# pendulumControl.net
KiCad netlist of a schematic drawn in EAGLE
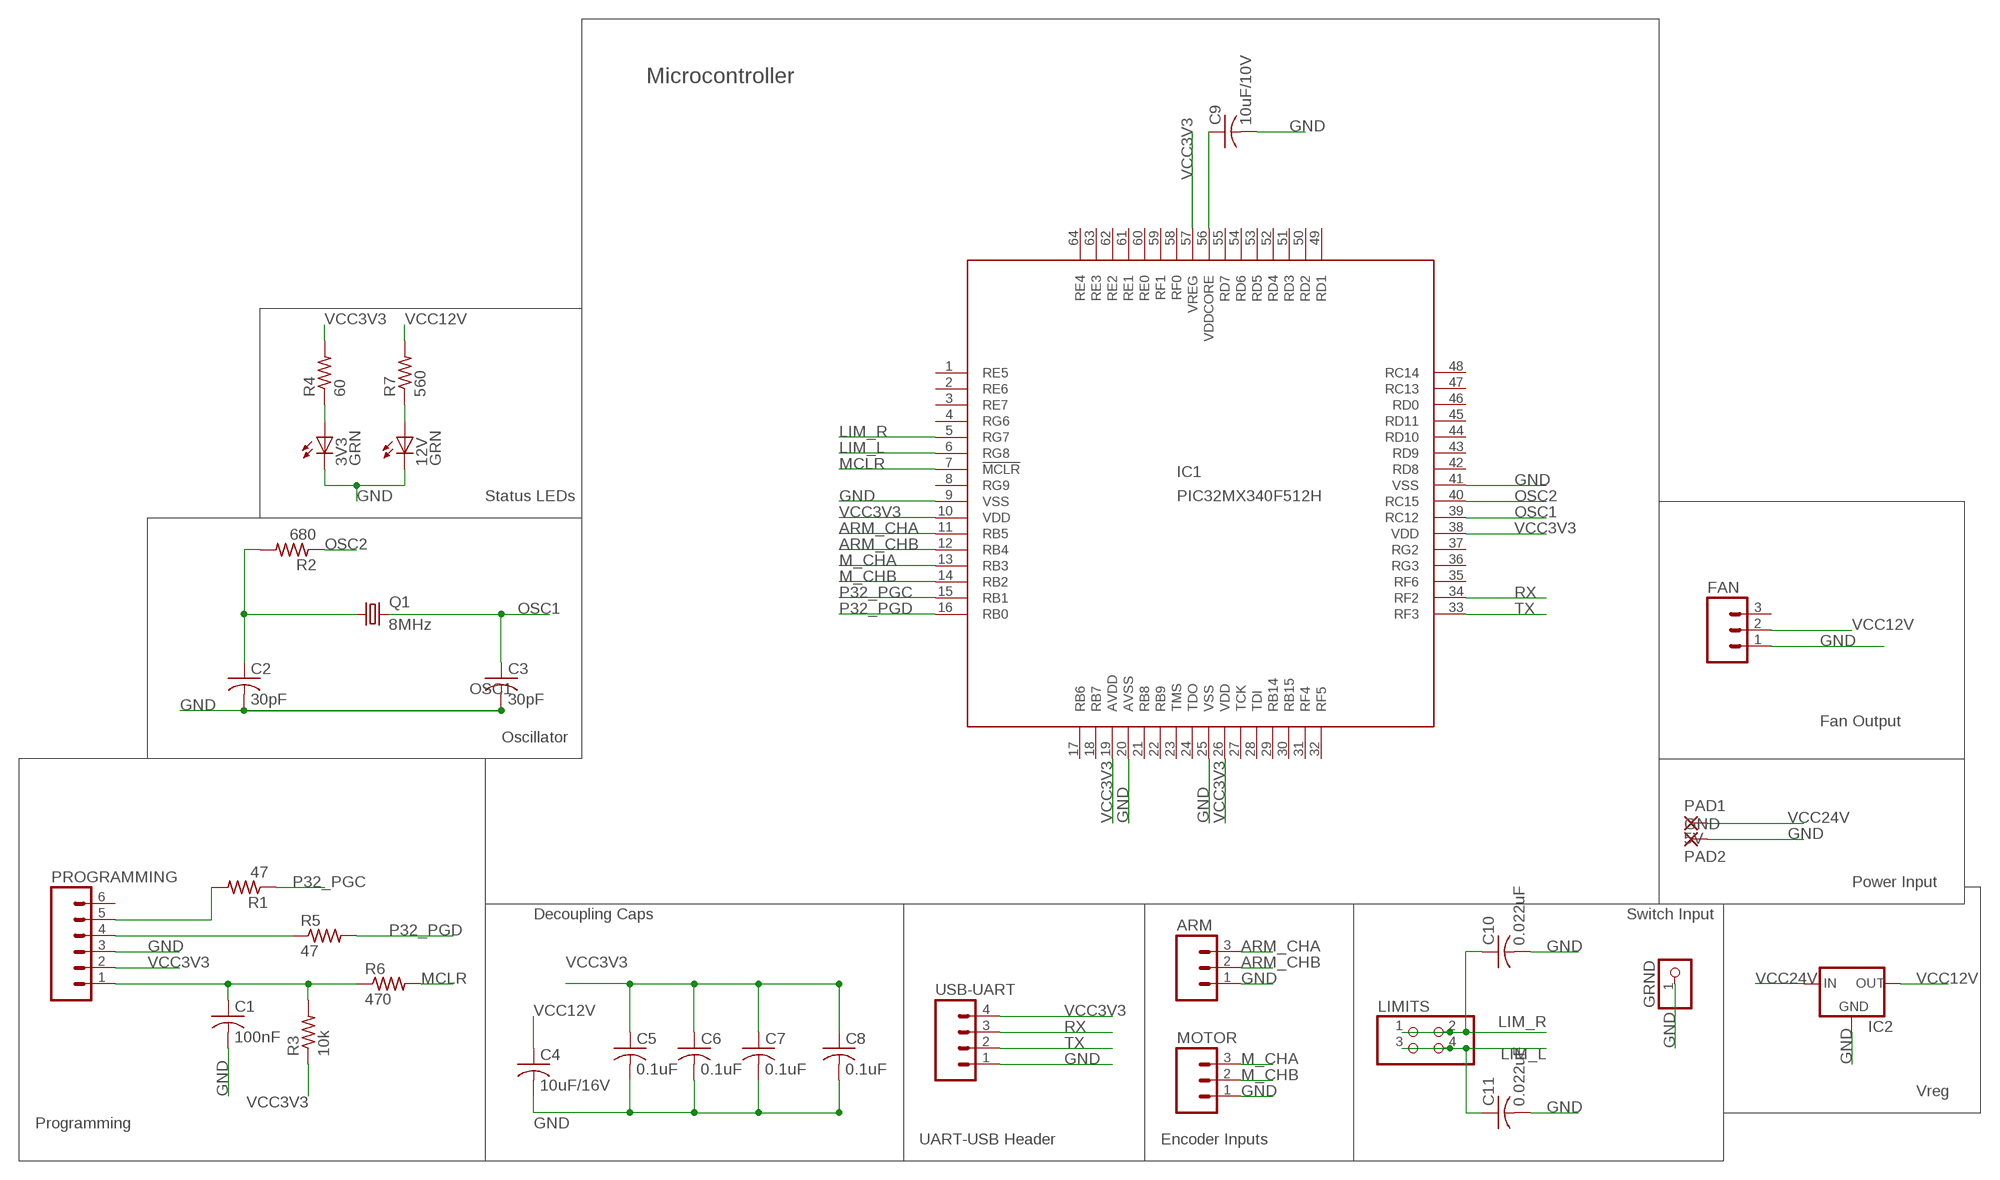
[diagram p0: schematic, sheet 1]

(export (version "E")
  (design (tool "Eeschema 10.0.6"))
  (components
    (comp (ref "3V3")
      (value "GRN")
      (footprint "eagle-import:CHIP-LED0805")
      (libsource (lib "eagle-import") (part "LEDCHIP-LED0805"))
    )
    (comp (ref "12V")
      (value "GRN")
      (footprint "eagle-import:CHIP-LED0805")
      (libsource (lib "eagle-import") (part "LEDCHIP-LED0805"))
    )
    (comp (ref "ARM")
      (value "M03PTH")
      (footprint "eagle-import:1X03")
      (libsource (lib "eagle-import") (part "M03PTH"))
    )
    (comp (ref "C1")
      (value "100nF")
      (footprint "eagle-import:C0805")
      (libsource (lib "eagle-import") (part "C-USC0805"))
    )
    (comp (ref "C2")
      (value "30pF")
      (footprint "eagle-import:C0805")
      (libsource (lib "eagle-import") (part "C-USC0805"))
    )
    (comp (ref "C3")
      (value "30pF")
      (footprint "eagle-import:C0805")
      (libsource (lib "eagle-import") (part "C-USC0805"))
    )
    (comp (ref "C4")
      (value "10uF/16V")
      (footprint "eagle-import:C0805")
      (libsource (lib "eagle-import") (part "C-USC0805"))
    )
    (comp (ref "C5")
      (value "0.1uF")
      (footprint "eagle-import:C0805")
      (libsource (lib "eagle-import") (part "C-USC0805"))
    )
    (comp (ref "C6")
      (value "0.1uF")
      (footprint "eagle-import:C0805")
      (libsource (lib "eagle-import") (part "resistor_C-USC0805"))
    )
    (comp (ref "C7")
      (value "0.1uF")
      (footprint "eagle-import:C0805")
      (libsource (lib "eagle-import") (part "resistor_C-USC0805"))
    )
    (comp (ref "C8")
      (value "0.1uF")
      (footprint "eagle-import:C0805")
      (libsource (lib "eagle-import") (part "resistor_C-USC0805"))
    )
    (comp (ref "C9")
      (value "10uF/10V")
      (footprint "eagle-import:C0805")
      (libsource (lib "eagle-import") (part "C-USC0805"))
    )
    (comp (ref "C10")
      (value "0.022uF")
      (footprint "eagle-import:C0805")
      (libsource (lib "eagle-import") (part "C-USC0805"))
    )
    (comp (ref "C11")
      (value "0.022uF")
      (footprint "eagle-import:C0805")
      (libsource (lib "eagle-import") (part "C-USC0805"))
    )
    (comp (ref "FAN")
      (value "M03POLAR")
      (footprint "eagle-import:MOLEX-1X3")
      (libsource (lib "eagle-import") (part "M03POLAR"))
    )
    (comp (ref "GRND")
      (value "PINHD-1X1")
      (footprint "eagle-import:1X01")
      (libsource (lib "eagle-import") (part "PINHD-1X1"))
    )
    (comp (ref "IC1")
      (value "PIC32MX340F512H")
      (footprint "eagle-import:TQFP64-10X10")
      (fields (field (name "MPN") "PIC32MX340F512H-80I/PT"))
      (libsource (lib "eagle-import") (part "PIC32MX340FH512"))
    )
    (comp (ref "IC2")
      (value "78MXXS")
      (footprint "eagle-import:78MXXS")
      (libsource (lib "eagle-import") (part "78MXXS"))
    )
    (comp (ref "LIMITS")
      (value "PINHD-2X2")
      (footprint "eagle-import:2X02")
      (libsource (lib "eagle-import") (part "PINHD-2X2"))
    )
    (comp (ref "MOTOR")
      (value "M03PTH")
      (footprint "eagle-import:1X03")
      (libsource (lib "eagle-import") (part "M03PTH"))
    )
    (comp (ref "PAD1")
      (value "5V")
      (footprint "eagle-import:3,81_1,4")
      (libsource (lib "eagle-import") (part "3,81/1,4"))
    )
    (comp (ref "PAD2")
      (value "GND")
      (footprint "eagle-import:3,81_1,4")
      (libsource (lib "eagle-import") (part "3,81/1,4"))
    )
    (comp (ref "PROGRAMMING")
      (value "M06FEMALE_LOCK")
      (footprint "eagle-import:1X06_FEMALE_LOCK.010")
      (libsource (lib "eagle-import") (part "M06FEMALE_LOCK"))
    )
    (comp (ref "Q1")
      (value "8MHz")
      (footprint "eagle-import:HC49_S")
      (libsource (lib "eagle-import") (part "CRYSTALHC49S"))
    )
    (comp (ref "R1")
      (value "47")
      (footprint "eagle-import:R0805")
      (libsource (lib "eagle-import") (part "resistor_R-US_R0805"))
    )
    (comp (ref "R2")
      (value "680")
      (footprint "eagle-import:R0805")
      (libsource (lib "eagle-import") (part "R-US_R0805"))
    )
    (comp (ref "R3")
      (value "10k")
      (footprint "eagle-import:R0805")
      (libsource (lib "eagle-import") (part "resistor_R-US_R0805"))
    )
    (comp (ref "R4")
      (value "60")
      (footprint "eagle-import:R0805")
      (libsource (lib "eagle-import") (part "R-US_R0805"))
    )
    (comp (ref "R5")
      (value "47")
      (footprint "eagle-import:R0805")
      (libsource (lib "eagle-import") (part "resistor_R-US_R0805"))
    )
    (comp (ref "R6")
      (value "470")
      (footprint "eagle-import:R0805")
      (libsource (lib "eagle-import") (part "resistor_R-US_R0805"))
    )
    (comp (ref "R7")
      (value "560")
      (footprint "eagle-import:R0805")
      (libsource (lib "eagle-import") (part "R-US_R0805"))
    )
    (comp (ref "USB-UART")
      (value "M04PTH")
      (footprint "eagle-import:1X04")
      (libsource (lib "eagle-import") (part "M04PTH"))
    )
  )
  (nets
    (net (code "1") (name "/ARM_CHA") (class "Default")
      (node (ref "ARM") (pin "3") (pinfunction "3_3") (pintype "passive"))
      (node (ref "IC1") (pin "11") (pinfunction "RB5_11") (pintype "bidirectional"))
    )
    (net (code "2") (name "/ARM_CHB") (class "Default")
      (node (ref "ARM") (pin "2") (pinfunction "2_2") (pintype "passive"))
      (node (ref "IC1") (pin "12") (pinfunction "RB4_12") (pintype "bidirectional"))
    )
    (net (code "3") (name "/GND") (class "Default")
      (node (ref "12V") (pin "C") (pinfunction "C_C") (pintype "passive"))
      (node (ref "3V3") (pin "C") (pinfunction "C_C") (pintype "passive"))
      (node (ref "ARM") (pin "1") (pinfunction "1_1") (pintype "passive"))
      (node (ref "C1") (pin "2") (pinfunction "2_2") (pintype "passive"))
      (node (ref "C10") (pin "2") (pinfunction "2_2") (pintype "passive"))
      (node (ref "C11") (pin "2") (pinfunction "2_2") (pintype "passive"))
      (node (ref "C2") (pin "2") (pinfunction "2_2") (pintype "passive"))
      (node (ref "C3") (pin "2") (pinfunction "2_2") (pintype "passive"))
      (node (ref "C4") (pin "2") (pinfunction "2_2") (pintype "passive"))
      (node (ref "C5") (pin "2") (pinfunction "2_2") (pintype "passive"))
      (node (ref "C6") (pin "2") (pinfunction "2_2") (pintype "passive"))
      (node (ref "C7") (pin "2") (pinfunction "2_2") (pintype "passive"))
      (node (ref "C8") (pin "2") (pinfunction "2_2") (pintype "passive"))
      (node (ref "C9") (pin "2") (pinfunction "2_2") (pintype "passive"))
      (node (ref "FAN") (pin "1") (pinfunction "1_1") (pintype "passive"))
      (node (ref "GRND") (pin "1") (pinfunction "1_1") (pintype "passive"))
      (node (ref "IC1") (pin "20") (pinfunction "AVSS_20") (pintype "power_in"))
      (node (ref "IC1") (pin "25") (pinfunction "VSS_25") (pintype "power_in"))
      (node (ref "IC1") (pin "41") (pinfunction "VSS_41") (pintype "power_in"))
      (node (ref "IC1") (pin "9") (pinfunction "VSS_9") (pintype "power_in"))
      (node (ref "IC2") (pin "GND") (pinfunction "GND_GND") (pintype "input"))
      (node (ref "MOTOR") (pin "1") (pinfunction "1_1") (pintype "passive"))
      (node (ref "PAD2") (pin "1") (pinfunction "P_1") (pintype "passive"))
      (node (ref "PROGRAMMING") (pin "3") (pinfunction "3_3") (pintype "passive"))
      (node (ref "USB-UART") (pin "1") (pinfunction "1_1") (pintype "passive"))
    )
    (net (code "4") (name "/LIM_L") (class "Default")
      (node (ref "C11") (pin "1") (pinfunction "1_1") (pintype "passive"))
      (node (ref "IC1") (pin "6") (pinfunction "RG8_6") (pintype "bidirectional"))
      (node (ref "LIMITS") (pin "3") (pinfunction "3_3") (pintype "passive"))
      (node (ref "LIMITS") (pin "4") (pinfunction "4_4") (pintype "passive"))
    )
    (net (code "5") (name "/LIM_R") (class "Default")
      (node (ref "C10") (pin "1") (pinfunction "1_1") (pintype "passive"))
      (node (ref "IC1") (pin "5") (pinfunction "RG7_5") (pintype "bidirectional"))
      (node (ref "LIMITS") (pin "1") (pinfunction "1_1") (pintype "passive"))
      (node (ref "LIMITS") (pin "2") (pinfunction "2_2") (pintype "passive"))
    )
    (net (code "6") (name "/MCLR") (class "Default")
      (node (ref "IC1") (pin "7") (pinfunction "~{MCLR}_7") (pintype "input"))
      (node (ref "R6") (pin "2") (pinfunction "2_2") (pintype "passive"))
    )
    (net (code "7") (name "/M_CHA") (class "Default")
      (node (ref "IC1") (pin "13") (pinfunction "RB3_13") (pintype "bidirectional"))
      (node (ref "MOTOR") (pin "3") (pinfunction "3_3") (pintype "passive"))
    )
    (net (code "8") (name "/M_CHB") (class "Default")
      (node (ref "IC1") (pin "14") (pinfunction "RB2_14") (pintype "bidirectional"))
      (node (ref "MOTOR") (pin "2") (pinfunction "2_2") (pintype "passive"))
    )
    (net (code "9") (name "/OSC1") (class "Default")
      (node (ref "C3") (pin "1") (pinfunction "1_1") (pintype "passive"))
      (node (ref "IC1") (pin "39") (pinfunction "RC12_39") (pintype "bidirectional"))
      (node (ref "Q1") (pin "2") (pinfunction "2_2") (pintype "passive"))
    )
    (net (code "10") (name "/OSC2") (class "Default")
      (node (ref "IC1") (pin "40") (pinfunction "RC15_40") (pintype "bidirectional"))
      (node (ref "R2") (pin "1") (pinfunction "1_1") (pintype "passive"))
    )
    (net (code "11") (name "/P32_PGC") (class "Default")
      (node (ref "IC1") (pin "15") (pinfunction "RB1_15") (pintype "bidirectional"))
      (node (ref "R1") (pin "1") (pinfunction "1_1") (pintype "passive"))
    )
    (net (code "12") (name "/P32_PGD") (class "Default")
      (node (ref "IC1") (pin "16") (pinfunction "RB0_16") (pintype "bidirectional"))
      (node (ref "R5") (pin "2") (pinfunction "2_2") (pintype "passive"))
    )
    (net (code "13") (name "/RX") (class "Default")
      (node (ref "IC1") (pin "34") (pinfunction "RF2_34") (pintype "bidirectional"))
      (node (ref "USB-UART") (pin "3") (pinfunction "3_3") (pintype "passive"))
    )
    (net (code "14") (name "/TX") (class "Default")
      (node (ref "IC1") (pin "33") (pinfunction "RF3_33") (pintype "bidirectional"))
      (node (ref "USB-UART") (pin "2") (pinfunction "2_2") (pintype "passive"))
    )
    (net (code "15") (name "/VCC3V3") (class "Default")
      (node (ref "C5") (pin "1") (pinfunction "1_1") (pintype "passive"))
      (node (ref "C6") (pin "1") (pinfunction "1_1") (pintype "passive"))
      (node (ref "C7") (pin "1") (pinfunction "1_1") (pintype "passive"))
      (node (ref "C8") (pin "1") (pinfunction "1_1") (pintype "passive"))
      (node (ref "IC1") (pin "10") (pinfunction "VDD_10") (pintype "power_in"))
      (node (ref "IC1") (pin "19") (pinfunction "AVDD_19") (pintype "power_in"))
      (node (ref "IC1") (pin "26") (pinfunction "VDD_26") (pintype "power_in"))
      (node (ref "IC1") (pin "38") (pinfunction "VDD_38") (pintype "power_in"))
      (node (ref "IC1") (pin "57") (pinfunction "VREG_57") (pintype "passive"))
      (node (ref "PROGRAMMING") (pin "2") (pinfunction "2_2") (pintype "passive"))
      (node (ref "R3") (pin "1") (pinfunction "1_1") (pintype "passive"))
      (node (ref "R4") (pin "2") (pinfunction "2_2") (pintype "passive"))
      (node (ref "USB-UART") (pin "4") (pinfunction "4_4") (pintype "passive"))
    )
    (net (code "16") (name "/VCC12V") (class "Default")
      (node (ref "C4") (pin "1") (pinfunction "1_1") (pintype "passive"))
      (node (ref "FAN") (pin "2") (pinfunction "2_2") (pintype "passive"))
      (node (ref "IC2") (pin "OUT") (pinfunction "OUT_OUT") (pintype "passive"))
      (node (ref "R7") (pin "2") (pinfunction "2_2") (pintype "passive"))
    )
    (net (code "17") (name "/VCC24V") (class "Default")
      (node (ref "IC2") (pin "IN") (pinfunction "IN_IN") (pintype "input"))
      (node (ref "PAD1") (pin "1") (pinfunction "P_1") (pintype "passive"))
    )
    (net (code "18") (name "Net-(3V3-PadA)") (class "Default")
      (node (ref "3V3") (pin "A") (pinfunction "A_A") (pintype "passive"))
      (node (ref "R4") (pin "1") (pinfunction "1_1") (pintype "passive"))
    )
    (net (code "19") (name "Net-(12V-PadA)") (class "Default")
      (node (ref "12V") (pin "A") (pinfunction "A_A") (pintype "passive"))
      (node (ref "R7") (pin "1") (pinfunction "1_1") (pintype "passive"))
    )
    (net (code "20") (name "Net-(C1-Pad1)") (class "Default")
      (node (ref "C1") (pin "1") (pinfunction "1_1") (pintype "passive"))
      (node (ref "PROGRAMMING") (pin "1") (pinfunction "1_1") (pintype "passive"))
      (node (ref "R3") (pin "2") (pinfunction "2_2") (pintype "passive"))
      (node (ref "R6") (pin "1") (pinfunction "1_1") (pintype "passive"))
    )
    (net (code "21") (name "Net-(C2-Pad1)") (class "Default")
      (node (ref "C2") (pin "1") (pinfunction "1_1") (pintype "passive"))
      (node (ref "Q1") (pin "1") (pinfunction "1_1") (pintype "passive"))
      (node (ref "R2") (pin "2") (pinfunction "2_2") (pintype "passive"))
    )
    (net (code "22") (name "Net-(IC1-VDDCORE)") (class "Default")
      (node (ref "C9") (pin "1") (pinfunction "1_1") (pintype "passive"))
      (node (ref "IC1") (pin "56") (pinfunction "VDDCORE_56") (pintype "power_in"))
    )
    (net (code "23") (name "Net-(PROGRAMMING-Pad4)") (class "Default")
      (node (ref "PROGRAMMING") (pin "4") (pinfunction "4_4") (pintype "passive"))
      (node (ref "R5") (pin "1") (pinfunction "1_1") (pintype "passive"))
    )
    (net (code "24") (name "Net-(PROGRAMMING-Pad5)") (class "Default")
      (node (ref "PROGRAMMING") (pin "5") (pinfunction "5_5") (pintype "passive"))
      (node (ref "R1") (pin "2") (pinfunction "2_2") (pintype "passive"))
    )
    (net (code "25") (name "unconnected-(FAN-Pad3)") (class "Default")
      (node (ref "FAN") (pin "3") (pinfunction "3_3") (pintype "passive"))
    )
    (net (code "26") (name "unconnected-(IC1-RB6-Pad17)") (class "Default")
      (node (ref "IC1") (pin "17") (pinfunction "RB6_17") (pintype "bidirectional"))
    )
    (net (code "27") (name "unconnected-(IC1-RB7-Pad18)") (class "Default")
      (node (ref "IC1") (pin "18") (pinfunction "RB7_18") (pintype "bidirectional"))
    )
    (net (code "28") (name "unconnected-(IC1-RB8-Pad21)") (class "Default")
      (node (ref "IC1") (pin "21") (pinfunction "RB8_21") (pintype "bidirectional"))
    )
    (net (code "29") (name "unconnected-(IC1-RB9-Pad22)") (class "Default")
      (node (ref "IC1") (pin "22") (pinfunction "RB9_22") (pintype "bidirectional"))
    )
    (net (code "30") (name "unconnected-(IC1-RB14-Pad29)") (class "Default")
      (node (ref "IC1") (pin "29") (pinfunction "RB14_29") (pintype "bidirectional"))
    )
    (net (code "31") (name "unconnected-(IC1-RB15-Pad30)") (class "Default")
      (node (ref "IC1") (pin "30") (pinfunction "RB15_30") (pintype "bidirectional"))
    )
    (net (code "32") (name "unconnected-(IC1-RC13-Pad47)") (class "Default")
      (node (ref "IC1") (pin "47") (pinfunction "RC13_47") (pintype "bidirectional"))
    )
    (net (code "33") (name "unconnected-(IC1-RC14-Pad48)") (class "Default")
      (node (ref "IC1") (pin "48") (pinfunction "RC14_48") (pintype "bidirectional"))
    )
    (net (code "34") (name "unconnected-(IC1-RD0-Pad46)") (class "Default")
      (node (ref "IC1") (pin "46") (pinfunction "RD0_46") (pintype "bidirectional"))
    )
    (net (code "35") (name "unconnected-(IC1-RD1-Pad49)") (class "Default")
      (node (ref "IC1") (pin "49") (pinfunction "RD1_49") (pintype "bidirectional"))
    )
    (net (code "36") (name "unconnected-(IC1-RD2-Pad50)") (class "Default")
      (node (ref "IC1") (pin "50") (pinfunction "RD2_50") (pintype "bidirectional"))
    )
    (net (code "37") (name "unconnected-(IC1-RD3-Pad51)") (class "Default")
      (node (ref "IC1") (pin "51") (pinfunction "RD3_51") (pintype "bidirectional"))
    )
    (net (code "38") (name "unconnected-(IC1-RD4-Pad52)") (class "Default")
      (node (ref "IC1") (pin "52") (pinfunction "RD4_52") (pintype "bidirectional"))
    )
    (net (code "39") (name "unconnected-(IC1-RD5-Pad53)") (class "Default")
      (node (ref "IC1") (pin "53") (pinfunction "RD5_53") (pintype "bidirectional"))
    )
    (net (code "40") (name "unconnected-(IC1-RD6-Pad54)") (class "Default")
      (node (ref "IC1") (pin "54") (pinfunction "RD6_54") (pintype "bidirectional"))
    )
    (net (code "41") (name "unconnected-(IC1-RD7-Pad55)") (class "Default")
      (node (ref "IC1") (pin "55") (pinfunction "RD7_55") (pintype "bidirectional"))
    )
    (net (code "42") (name "unconnected-(IC1-RD8-Pad42)") (class "Default")
      (node (ref "IC1") (pin "42") (pinfunction "RD8_42") (pintype "bidirectional"))
    )
    (net (code "43") (name "unconnected-(IC1-RD9-Pad43)") (class "Default")
      (node (ref "IC1") (pin "43") (pinfunction "RD9_43") (pintype "bidirectional"))
    )
    (net (code "44") (name "unconnected-(IC1-RD10-Pad44)") (class "Default")
      (node (ref "IC1") (pin "44") (pinfunction "RD10_44") (pintype "bidirectional"))
    )
    (net (code "45") (name "unconnected-(IC1-RD11-Pad45)") (class "Default")
      (node (ref "IC1") (pin "45") (pinfunction "RD11_45") (pintype "bidirectional"))
    )
    (net (code "46") (name "unconnected-(IC1-RE0-Pad60)") (class "Default")
      (node (ref "IC1") (pin "60") (pinfunction "RE0_60") (pintype "bidirectional"))
    )
    (net (code "47") (name "unconnected-(IC1-RE1-Pad61)") (class "Default")
      (node (ref "IC1") (pin "61") (pinfunction "RE1_61") (pintype "bidirectional"))
    )
    (net (code "48") (name "unconnected-(IC1-RE2-Pad62)") (class "Default")
      (node (ref "IC1") (pin "62") (pinfunction "RE2_62") (pintype "bidirectional"))
    )
    (net (code "49") (name "unconnected-(IC1-RE3-Pad63)") (class "Default")
      (node (ref "IC1") (pin "63") (pinfunction "RE3_63") (pintype "bidirectional"))
    )
    (net (code "50") (name "unconnected-(IC1-RE4-Pad64)") (class "Default")
      (node (ref "IC1") (pin "64") (pinfunction "RE4_64") (pintype "bidirectional"))
    )
    (net (code "51") (name "unconnected-(IC1-RE5-Pad1)") (class "Default")
      (node (ref "IC1") (pin "1") (pinfunction "RE5_1") (pintype "bidirectional"))
    )
    (net (code "52") (name "unconnected-(IC1-RE6-Pad2)") (class "Default")
      (node (ref "IC1") (pin "2") (pinfunction "RE6_2") (pintype "bidirectional"))
    )
    (net (code "53") (name "unconnected-(IC1-RE7-Pad3)") (class "Default")
      (node (ref "IC1") (pin "3") (pinfunction "RE7_3") (pintype "bidirectional"))
    )
    (net (code "54") (name "unconnected-(IC1-RF0-Pad58)") (class "Default")
      (node (ref "IC1") (pin "58") (pinfunction "RF0_58") (pintype "bidirectional"))
    )
    (net (code "55") (name "unconnected-(IC1-RF1-Pad59)") (class "Default")
      (node (ref "IC1") (pin "59") (pinfunction "RF1_59") (pintype "bidirectional"))
    )
    (net (code "56") (name "unconnected-(IC1-RF4-Pad31)") (class "Default")
      (node (ref "IC1") (pin "31") (pinfunction "RF4_31") (pintype "bidirectional"))
    )
    (net (code "57") (name "unconnected-(IC1-RF5-Pad32)") (class "Default")
      (node (ref "IC1") (pin "32") (pinfunction "RF5_32") (pintype "bidirectional"))
    )
    (net (code "58") (name "unconnected-(IC1-RF6-Pad35)") (class "Default")
      (node (ref "IC1") (pin "35") (pinfunction "RF6_35") (pintype "bidirectional"))
    )
    (net (code "59") (name "unconnected-(IC1-RG2-Pad37)") (class "Default")
      (node (ref "IC1") (pin "37") (pinfunction "RG2_37") (pintype "bidirectional"))
    )
    (net (code "60") (name "unconnected-(IC1-RG3-Pad36)") (class "Default")
      (node (ref "IC1") (pin "36") (pinfunction "RG3_36") (pintype "bidirectional"))
    )
    (net (code "61") (name "unconnected-(IC1-RG6-Pad4)") (class "Default")
      (node (ref "IC1") (pin "4") (pinfunction "RG6_4") (pintype "bidirectional"))
    )
    (net (code "62") (name "unconnected-(IC1-RG9-Pad8)") (class "Default")
      (node (ref "IC1") (pin "8") (pinfunction "RG9_8") (pintype "bidirectional"))
    )
    (net (code "63") (name "unconnected-(IC1-TCK-Pad27)") (class "Default")
      (node (ref "IC1") (pin "27") (pinfunction "TCK_27") (pintype "input"))
    )
    (net (code "64") (name "unconnected-(IC1-TDI-Pad28)") (class "Default")
      (node (ref "IC1") (pin "28") (pinfunction "TDI_28") (pintype "input"))
    )
    (net (code "65") (name "unconnected-(IC1-TDO-Pad24)") (class "Default")
      (node (ref "IC1") (pin "24") (pinfunction "TDO_24") (pintype "output"))
    )
    (net (code "66") (name "unconnected-(IC1-TMS-Pad23)") (class "Default")
      (node (ref "IC1") (pin "23") (pinfunction "TMS_23") (pintype "input"))
    )
    (net (code "67") (name "unconnected-(PROGRAMMING-Pad6)") (class "Default")
      (node (ref "PROGRAMMING") (pin "6") (pinfunction "6_6") (pintype "passive"))
    )
  )
)
